# MainBlock.net
KiCad netlist of a schematic drawn in Altium Designer
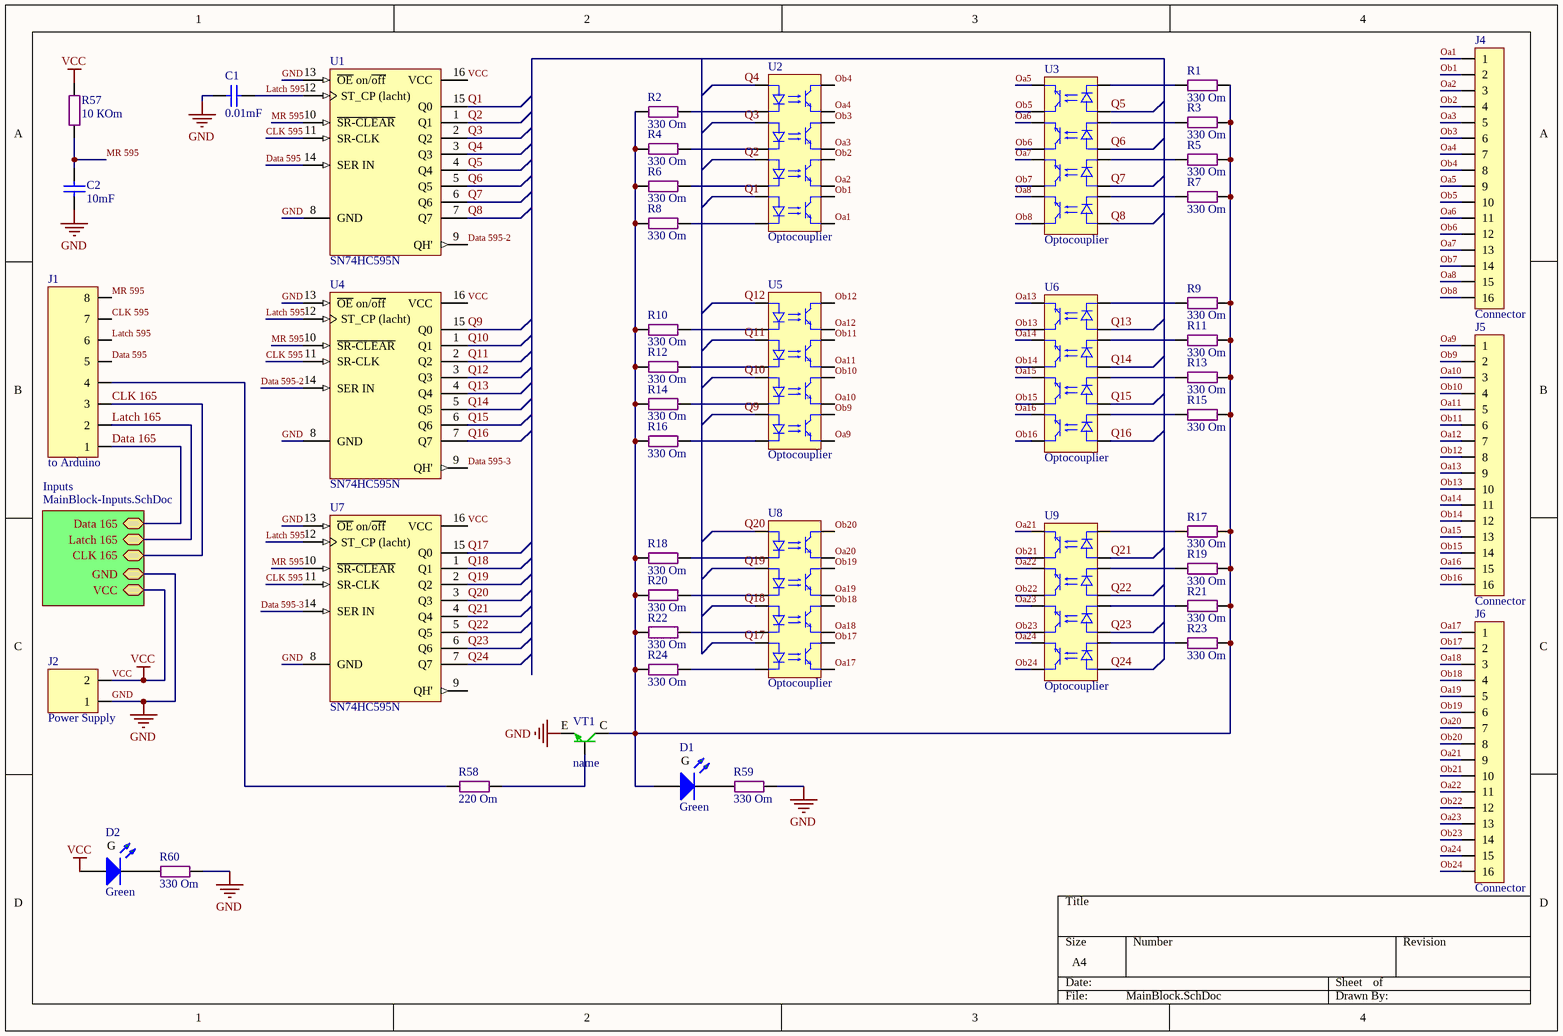
[diagram p0: MainBlock.SchDoc]

(export (version "E")
  (design (tool "Eeschema 10.0.6"))
  (components
    (comp (ref "C1")
      (value "0.01mF")
      (footprint "bj Lib:Cap (3p)")
      (description "Capacitor")
      (libsource (lib "bj Lib") (part "Cap"))
    )
    (comp (ref "C2")
      (value "10mF")
      (footprint "bj Lib:Cap p2.54mm (2p)")
      (description "Capacitor")
      (libsource (lib "ss_ServersControl") (part "Cap"))
    )
    (comp (ref "D1")
      (value "Green")
      (footprint "LED:LED SMD 0805 Green")
      (description "?2v ?20mA")
      (libsource (lib "LED") (part "Led SMD 0805 Green"))
    )
    (comp (ref "D2")
      (value "Green")
      (footprint "LED:LED SMD 0805 Green")
      (description "?2v ?20mA")
      (libsource (lib "LED") (part "Led SMD 0805 Green"))
    )
    (comp (ref "J1")
      (value "to Arduino")
      (footprint "bj Lib:Line 2.54 x 8")
      (description "8pin Connector")
      (libsource (lib "bj Lib") (part "Connector ( 8 pin )"))
    )
    (comp (ref "J2")
      (value "Power Supply")
      (footprint "bj Lib:Line 2.54 x 2")
      (description "8pin Connector")
      (libsource (lib "bj Lib") (part "Connector ( 2 pin )"))
    )
    (comp (ref "J4")
      (value "Connector")
      (footprint "bj Lib:LINE 2.54 x 8D mirrored")
      (description "16pin Connector")
      (libsource (lib "ss_ServersControl") (part "Connector Dbl ( 16 pin )"))
    )
    (comp (ref "J5")
      (value "Connector")
      (footprint "bj Lib:LINE 2.54 x 8D mirrored")
      (description "16pin Connector")
      (libsource (lib "ss_ServersControl") (part "Connector Dbl ( 16 pin )"))
    )
    (comp (ref "J6")
      (value "Connector")
      (footprint "bj Lib:LINE 2.54 x 8D mirrored")
      (description "16pin Connector")
      (libsource (lib "ss_ServersControl") (part "Connector Dbl ( 16 pin )"))
    )
    (comp (ref "R1")
      (value "330 Om")
      (footprint "Res p7.62 (4p)")
      (libsource (lib "bj Lib") (part "Resistor"))
    )
    (comp (ref "R2")
      (value "330 Om")
      (footprint "Res p7.62 (4p)")
      (libsource (lib "bj Lib") (part "Resistor"))
    )
    (comp (ref "R3")
      (value "330 Om")
      (footprint "Res p7.62 (4p)")
      (libsource (lib "bj Lib") (part "Resistor"))
    )
    (comp (ref "R4")
      (value "330 Om")
      (footprint "Res p7.62 (4p)")
      (libsource (lib "bj Lib") (part "Resistor"))
    )
    (comp (ref "R5")
      (value "330 Om")
      (footprint "Res p7.62 (4p)")
      (libsource (lib "bj Lib") (part "Resistor"))
    )
    (comp (ref "R6")
      (value "330 Om")
      (footprint "Res p7.62 (4p)")
      (libsource (lib "bj Lib") (part "Resistor"))
    )
    (comp (ref "R7")
      (value "330 Om")
      (footprint "Res p7.62 (4p)")
      (libsource (lib "bj Lib") (part "Resistor"))
    )
    (comp (ref "R8")
      (value "330 Om")
      (footprint "Res p7.62 (4p)")
      (libsource (lib "bj Lib") (part "Resistor"))
    )
    (comp (ref "R9")
      (value "330 Om")
      (footprint "Res p7.62 (4p)")
      (libsource (lib "bj Lib") (part "Resistor"))
    )
    (comp (ref "R10")
      (value "330 Om")
      (footprint "Res p7.62 (4p)")
      (libsource (lib "bj Lib") (part "Resistor"))
    )
    (comp (ref "R11")
      (value "330 Om")
      (footprint "Res p7.62 (4p)")
      (libsource (lib "bj Lib") (part "Resistor"))
    )
    (comp (ref "R12")
      (value "330 Om")
      (footprint "Res p7.62 (4p)")
      (libsource (lib "bj Lib") (part "Resistor"))
    )
    (comp (ref "R13")
      (value "330 Om")
      (footprint "Res p7.62 (4p)")
      (libsource (lib "bj Lib") (part "Resistor"))
    )
    (comp (ref "R14")
      (value "330 Om")
      (footprint "Res p7.62 (4p)")
      (libsource (lib "bj Lib") (part "Resistor"))
    )
    (comp (ref "R15")
      (value "330 Om")
      (footprint "Res p7.62 (4p)")
      (libsource (lib "bj Lib") (part "Resistor"))
    )
    (comp (ref "R16")
      (value "330 Om")
      (footprint "Res p7.62 (4p)")
      (libsource (lib "bj Lib") (part "Resistor"))
    )
    (comp (ref "R17")
      (value "330 Om")
      (footprint "Res p7.62 (4p)")
      (libsource (lib "bj Lib") (part "Resistor"))
    )
    (comp (ref "R18")
      (value "330 Om")
      (footprint "Res p7.62 (4p)")
      (libsource (lib "bj Lib") (part "Resistor"))
    )
    (comp (ref "R19")
      (value "330 Om")
      (footprint "Res p7.62 (4p)")
      (libsource (lib "bj Lib") (part "Resistor"))
    )
    (comp (ref "R20")
      (value "330 Om")
      (footprint "Res p7.62 (4p)")
      (libsource (lib "bj Lib") (part "Resistor"))
    )
    (comp (ref "R21")
      (value "330 Om")
      (footprint "Res p7.62 (4p)")
      (libsource (lib "bj Lib") (part "Resistor"))
    )
    (comp (ref "R22")
      (value "330 Om")
      (footprint "Res p7.62 (4p)")
      (libsource (lib "bj Lib") (part "Resistor"))
    )
    (comp (ref "R23")
      (value "330 Om")
      (footprint "Res p7.62 (4p)")
      (libsource (lib "bj Lib") (part "Resistor"))
    )
    (comp (ref "R24")
      (value "330 Om")
      (footprint "Res p7.62 (4p)")
      (libsource (lib "bj Lib") (part "Resistor"))
    )
    (comp (ref "R57")
      (value "10 КOm")
      (footprint "Res p7.62 (4p)")
      (libsource (lib "ss_ServersControl") (part "Resistor"))
    )
    (comp (ref "R58")
      (value "220 Om")
      (footprint "Res p7.62 (4p)")
      (libsource (lib "ss_ServersControl") (part "Resistor"))
    )
    (comp (ref "R59")
      (value "330 Om")
      (footprint "bj Lib:SMD 0603 (1608)")
      (libsource (lib "ss_ServersControl") (part "Resistor"))
    )
    (comp (ref "R60")
      (value "330 Om")
      (footprint "bj Lib:SMD 0603 (1608)")
      (libsource (lib "ss_ServersControl") (part "Resistor"))
    )
    (comp (ref "U1")
      (value "SN74HC595N")
      (footprint "bj Lib:DIP16")
      (description "8-Bit Shift Register with 3-State Output Registers")
      (fields (field (name "PUBLISHER") "Altium Limited"))
      (libsource (lib "bj Lib") (part "SN74HC595N"))
    )
    (comp (ref "U2")
      (value "Optocouplier")
      (footprint "bj Lib:DIP16")
      (description "4x channel")
      (libsource (lib "bj Lib") (part "Optocouplier 4x"))
    )
    (comp (ref "U3")
      (value "Optocouplier")
      (footprint "bj Lib:DIP16")
      (description "4x channel")
      (libsource (lib "bj Lib") (part "Optocouplier 4x"))
    )
    (comp (ref "U4")
      (value "SN74HC595N")
      (footprint "bj Lib:DIP16")
      (description "8-Bit Shift Register with 3-State Output Registers")
      (fields (field (name "PUBLISHER") "Altium Limited"))
      (libsource (lib "bj Lib") (part "SN74HC595N"))
    )
    (comp (ref "U5")
      (value "Optocouplier")
      (footprint "bj Lib:DIP16")
      (description "4x channel")
      (libsource (lib "bj Lib") (part "Optocouplier 4x"))
    )
    (comp (ref "U6")
      (value "Optocouplier")
      (footprint "bj Lib:DIP16")
      (description "4x channel")
      (libsource (lib "bj Lib") (part "Optocouplier 4x"))
    )
    (comp (ref "U7")
      (value "SN74HC595N")
      (footprint "bj Lib:DIP16")
      (description "8-Bit Shift Register with 3-State Output Registers")
      (fields (field (name "PUBLISHER") "Altium Limited"))
      (libsource (lib "bj Lib") (part "SN74HC595N"))
    )
    (comp (ref "U8")
      (value "Optocouplier")
      (footprint "bj Lib:DIP16")
      (description "4x channel")
      (libsource (lib "bj Lib") (part "Optocouplier 4x"))
    )
    (comp (ref "U9")
      (value "Optocouplier")
      (footprint "bj Lib:DIP16")
      (description "4x channel")
      (libsource (lib "bj Lib") (part "Optocouplier 4x"))
    )
    (comp (ref "VT1") (value "name") (footprint "Trnstr (3p) ECB") (libsource (lib "bj Lib") (part "NPN")))
  )
  (nets
    (net (code "1") (name "/CLK 165") (class "Default")
      (node (ref "J1") (pin "3") (pinfunction "3_3") (pintype "passive"))
    )
    (net (code "2") (name "/CLK 595") (class "Default")
      (node (ref "J1") (pin "7") (pinfunction "7_7") (pintype "passive"))
      (node (ref "U1") (pin "11") (pinfunction "SR-CLK_11") (pintype "input"))
      (node (ref "U4") (pin "11") (pinfunction "SR-CLK_11") (pintype "input"))
      (node (ref "U7") (pin "11") (pinfunction "SR-CLK_11") (pintype "input"))
    )
    (net (code "3") (name "/Data 165") (class "Default")
      (node (ref "J1") (pin "1") (pinfunction "1_1") (pintype "passive"))
    )
    (net (code "4") (name "/Data 595") (class "Default")
      (node (ref "J1") (pin "5") (pinfunction "5_5") (pintype "passive"))
      (node (ref "U1") (pin "14") (pinfunction "SER_IN_14") (pintype "input"))
    )
    (net (code "5") (name "/Data 595-2") (class "Default")
      (node (ref "U1") (pin "9") (pinfunction "QH'_9") (pintype "output"))
      (node (ref "U4") (pin "14") (pinfunction "SER_IN_14") (pintype "input"))
    )
    (net (code "6") (name "/Data 595-3") (class "Default")
      (node (ref "U4") (pin "9") (pinfunction "QH'_9") (pintype "output"))
      (node (ref "U7") (pin "14") (pinfunction "SER_IN_14") (pintype "input"))
    )
    (net (code "7") (name "/Latch 165") (class "Default")
      (node (ref "J1") (pin "2") (pinfunction "2_2") (pintype "passive"))
    )
    (net (code "8") (name "/Latch 595") (class "Default")
      (node (ref "C1") (pin "1") (pinfunction "1_1") (pintype "passive"))
      (node (ref "J1") (pin "6") (pinfunction "6_6") (pintype "passive"))
      (node (ref "U1") (pin "12") (pinfunction "ST_CP_(lacht)_12") (pintype "input"))
      (node (ref "U4") (pin "12") (pinfunction "ST_CP_(lacht)_12") (pintype "input"))
      (node (ref "U7") (pin "12") (pinfunction "ST_CP_(lacht)_12") (pintype "input"))
    )
    (net (code "9") (name "/MR 595") (class "Default")
      (node (ref "C2") (pin "2") (pinfunction "2_2") (pintype "passive"))
      (node (ref "J1") (pin "8") (pinfunction "8_8") (pintype "passive"))
      (node (ref "R57") (pin "2") (pinfunction "2_2") (pintype "passive"))
      (node (ref "U1") (pin "10") (pinfunction "~{SR-CLEAR}_10") (pintype "input"))
      (node (ref "U4") (pin "10") (pinfunction "~{SR-CLEAR}_10") (pintype "input"))
      (node (ref "U7") (pin "10") (pinfunction "~{SR-CLEAR}_10") (pintype "input"))
    )
    (net (code "10") (name "/Oa1") (class "Default")
      (node (ref "J4") (pin "1") (pinfunction "1_1") (pintype "passive"))
      (node (ref "U2") (pin "9") (pinfunction "9_9") (pintype "passive"))
    )
    (net (code "11") (name "/Oa2") (class "Default")
      (node (ref "J4") (pin "3") (pinfunction "3_3") (pintype "passive"))
      (node (ref "U2") (pin "11") (pinfunction "11_11") (pintype "passive"))
    )
    (net (code "12") (name "/Oa3") (class "Default")
      (node (ref "J4") (pin "5") (pinfunction "5_5") (pintype "passive"))
      (node (ref "U2") (pin "13") (pinfunction "13_13") (pintype "passive"))
    )
    (net (code "13") (name "/Oa4") (class "Default")
      (node (ref "J4") (pin "7") (pinfunction "7_7") (pintype "passive"))
      (node (ref "U2") (pin "15") (pinfunction "15_15") (pintype "passive"))
    )
    (net (code "14") (name "/Oa5") (class "Default")
      (node (ref "J4") (pin "9") (pinfunction "9_9") (pintype "passive"))
      (node (ref "U3") (pin "9") (pinfunction "9_9") (pintype "passive"))
    )
    (net (code "15") (name "/Oa6") (class "Default")
      (node (ref "J4") (pin "11") (pinfunction "11_11") (pintype "passive"))
      (node (ref "U3") (pin "11") (pinfunction "11_11") (pintype "passive"))
    )
    (net (code "16") (name "/Oa7") (class "Default")
      (node (ref "J4") (pin "13") (pinfunction "13_13") (pintype "passive"))
      (node (ref "U3") (pin "13") (pinfunction "13_13") (pintype "passive"))
    )
    (net (code "17") (name "/Oa8") (class "Default")
      (node (ref "J4") (pin "15") (pinfunction "15_15") (pintype "passive"))
      (node (ref "U3") (pin "15") (pinfunction "15_15") (pintype "passive"))
    )
    (net (code "18") (name "/Oa9") (class "Default")
      (node (ref "J5") (pin "1") (pinfunction "1_1") (pintype "passive"))
      (node (ref "U5") (pin "9") (pinfunction "9_9") (pintype "passive"))
    )
    (net (code "19") (name "/Oa10") (class "Default")
      (node (ref "J5") (pin "3") (pinfunction "3_3") (pintype "passive"))
      (node (ref "U5") (pin "11") (pinfunction "11_11") (pintype "passive"))
    )
    (net (code "20") (name "/Oa11") (class "Default")
      (node (ref "J5") (pin "5") (pinfunction "5_5") (pintype "passive"))
      (node (ref "U5") (pin "13") (pinfunction "13_13") (pintype "passive"))
    )
    (net (code "21") (name "/Oa12") (class "Default")
      (node (ref "J5") (pin "7") (pinfunction "7_7") (pintype "passive"))
      (node (ref "U5") (pin "15") (pinfunction "15_15") (pintype "passive"))
    )
    (net (code "22") (name "/Oa13") (class "Default")
      (node (ref "J5") (pin "9") (pinfunction "9_9") (pintype "passive"))
      (node (ref "U6") (pin "9") (pinfunction "9_9") (pintype "passive"))
    )
    (net (code "23") (name "/Oa14") (class "Default")
      (node (ref "J5") (pin "11") (pinfunction "11_11") (pintype "passive"))
      (node (ref "U6") (pin "11") (pinfunction "11_11") (pintype "passive"))
    )
    (net (code "24") (name "/Oa15") (class "Default")
      (node (ref "J5") (pin "13") (pinfunction "13_13") (pintype "passive"))
      (node (ref "U6") (pin "13") (pinfunction "13_13") (pintype "passive"))
    )
    (net (code "25") (name "/Oa16") (class "Default")
      (node (ref "J5") (pin "15") (pinfunction "15_15") (pintype "passive"))
      (node (ref "U6") (pin "15") (pinfunction "15_15") (pintype "passive"))
    )
    (net (code "26") (name "/Oa17") (class "Default")
      (node (ref "J6") (pin "1") (pinfunction "1_1") (pintype "passive"))
      (node (ref "U8") (pin "9") (pinfunction "9_9") (pintype "passive"))
    )
    (net (code "27") (name "/Oa18") (class "Default")
      (node (ref "J6") (pin "3") (pinfunction "3_3") (pintype "passive"))
      (node (ref "U8") (pin "11") (pinfunction "11_11") (pintype "passive"))
    )
    (net (code "28") (name "/Oa19") (class "Default")
      (node (ref "J6") (pin "5") (pinfunction "5_5") (pintype "passive"))
      (node (ref "U8") (pin "13") (pinfunction "13_13") (pintype "passive"))
    )
    (net (code "29") (name "/Oa20") (class "Default")
      (node (ref "J6") (pin "7") (pinfunction "7_7") (pintype "passive"))
      (node (ref "U8") (pin "15") (pinfunction "15_15") (pintype "passive"))
    )
    (net (code "30") (name "/Oa21") (class "Default")
      (node (ref "J6") (pin "9") (pinfunction "9_9") (pintype "passive"))
      (node (ref "U9") (pin "9") (pinfunction "9_9") (pintype "passive"))
    )
    (net (code "31") (name "/Oa22") (class "Default")
      (node (ref "J6") (pin "11") (pinfunction "11_11") (pintype "passive"))
      (node (ref "U9") (pin "11") (pinfunction "11_11") (pintype "passive"))
    )
    (net (code "32") (name "/Oa23") (class "Default")
      (node (ref "J6") (pin "13") (pinfunction "13_13") (pintype "passive"))
      (node (ref "U9") (pin "13") (pinfunction "13_13") (pintype "passive"))
    )
    (net (code "33") (name "/Oa24") (class "Default")
      (node (ref "J6") (pin "15") (pinfunction "15_15") (pintype "passive"))
      (node (ref "U9") (pin "15") (pinfunction "15_15") (pintype "passive"))
    )
    (net (code "34") (name "/Ob1") (class "Default")
      (node (ref "J4") (pin "2") (pinfunction "2_2") (pintype "passive"))
      (node (ref "U2") (pin "10") (pinfunction "10_10") (pintype "passive"))
    )
    (net (code "35") (name "/Ob2") (class "Default")
      (node (ref "J4") (pin "4") (pinfunction "4_4") (pintype "passive"))
      (node (ref "U2") (pin "12") (pinfunction "12_12") (pintype "passive"))
    )
    (net (code "36") (name "/Ob3") (class "Default")
      (node (ref "J4") (pin "6") (pinfunction "6_6") (pintype "passive"))
      (node (ref "U2") (pin "14") (pinfunction "14_14") (pintype "passive"))
    )
    (net (code "37") (name "/Ob4") (class "Default")
      (node (ref "J4") (pin "8") (pinfunction "8_8") (pintype "passive"))
      (node (ref "U2") (pin "16") (pinfunction "16_16") (pintype "passive"))
    )
    (net (code "38") (name "/Ob5") (class "Default")
      (node (ref "J4") (pin "10") (pinfunction "10_10") (pintype "passive"))
      (node (ref "U3") (pin "10") (pinfunction "10_10") (pintype "passive"))
    )
    (net (code "39") (name "/Ob6") (class "Default")
      (node (ref "J4") (pin "12") (pinfunction "12_12") (pintype "passive"))
      (node (ref "U3") (pin "12") (pinfunction "12_12") (pintype "passive"))
    )
    (net (code "40") (name "/Ob7") (class "Default")
      (node (ref "J4") (pin "14") (pinfunction "14_14") (pintype "passive"))
      (node (ref "U3") (pin "14") (pinfunction "14_14") (pintype "passive"))
    )
    (net (code "41") (name "/Ob8") (class "Default")
      (node (ref "J4") (pin "16") (pinfunction "16_16") (pintype "passive"))
      (node (ref "U3") (pin "16") (pinfunction "16_16") (pintype "passive"))
    )
    (net (code "42") (name "/Ob9") (class "Default")
      (node (ref "J5") (pin "2") (pinfunction "2_2") (pintype "passive"))
      (node (ref "U5") (pin "10") (pinfunction "10_10") (pintype "passive"))
    )
    (net (code "43") (name "/Ob10") (class "Default")
      (node (ref "J5") (pin "4") (pinfunction "4_4") (pintype "passive"))
      (node (ref "U5") (pin "12") (pinfunction "12_12") (pintype "passive"))
    )
    (net (code "44") (name "/Ob11") (class "Default")
      (node (ref "J5") (pin "6") (pinfunction "6_6") (pintype "passive"))
      (node (ref "U5") (pin "14") (pinfunction "14_14") (pintype "passive"))
    )
    (net (code "45") (name "/Ob12") (class "Default")
      (node (ref "J5") (pin "8") (pinfunction "8_8") (pintype "passive"))
      (node (ref "U5") (pin "16") (pinfunction "16_16") (pintype "passive"))
    )
    (net (code "46") (name "/Ob13") (class "Default")
      (node (ref "J5") (pin "10") (pinfunction "10_10") (pintype "passive"))
      (node (ref "U6") (pin "10") (pinfunction "10_10") (pintype "passive"))
    )
    (net (code "47") (name "/Ob14") (class "Default")
      (node (ref "J5") (pin "12") (pinfunction "12_12") (pintype "passive"))
      (node (ref "U6") (pin "12") (pinfunction "12_12") (pintype "passive"))
    )
    (net (code "48") (name "/Ob15") (class "Default")
      (node (ref "J5") (pin "14") (pinfunction "14_14") (pintype "passive"))
      (node (ref "U6") (pin "14") (pinfunction "14_14") (pintype "passive"))
    )
    (net (code "49") (name "/Ob16") (class "Default")
      (node (ref "J5") (pin "16") (pinfunction "16_16") (pintype "passive"))
      (node (ref "U6") (pin "16") (pinfunction "16_16") (pintype "passive"))
    )
    (net (code "50") (name "/Ob17") (class "Default")
      (node (ref "J6") (pin "2") (pinfunction "2_2") (pintype "passive"))
      (node (ref "U8") (pin "10") (pinfunction "10_10") (pintype "passive"))
    )
    (net (code "51") (name "/Ob18") (class "Default")
      (node (ref "J6") (pin "4") (pinfunction "4_4") (pintype "passive"))
      (node (ref "U8") (pin "12") (pinfunction "12_12") (pintype "passive"))
    )
    (net (code "52") (name "/Ob19") (class "Default")
      (node (ref "J6") (pin "6") (pinfunction "6_6") (pintype "passive"))
      (node (ref "U8") (pin "14") (pinfunction "14_14") (pintype "passive"))
    )
    (net (code "53") (name "/Ob20") (class "Default")
      (node (ref "J6") (pin "8") (pinfunction "8_8") (pintype "passive"))
      (node (ref "U8") (pin "16") (pinfunction "16_16") (pintype "passive"))
    )
    (net (code "54") (name "/Ob21") (class "Default")
      (node (ref "J6") (pin "10") (pinfunction "10_10") (pintype "passive"))
      (node (ref "U9") (pin "10") (pinfunction "10_10") (pintype "passive"))
    )
    (net (code "55") (name "/Ob22") (class "Default")
      (node (ref "J6") (pin "12") (pinfunction "12_12") (pintype "passive"))
      (node (ref "U9") (pin "12") (pinfunction "12_12") (pintype "passive"))
    )
    (net (code "56") (name "/Ob23") (class "Default")
      (node (ref "J6") (pin "14") (pinfunction "14_14") (pintype "passive"))
      (node (ref "U9") (pin "14") (pinfunction "14_14") (pintype "passive"))
    )
    (net (code "57") (name "/Ob24") (class "Default")
      (node (ref "J6") (pin "16") (pinfunction "16_16") (pintype "passive"))
      (node (ref "U9") (pin "16") (pinfunction "16_16") (pintype "passive"))
    )
    (net (code "58") (name "/Q1") (class "Default")
      (node (ref "U1") (pin "15") (pinfunction "Q0_15") (pintype "tri_state"))
      (node (ref "U2") (pin "7") (pinfunction "7_7") (pintype "passive"))
    )
    (net (code "59") (name "/Q2") (class "Default")
      (node (ref "U1") (pin "1") (pinfunction "Q1_1") (pintype "tri_state"))
      (node (ref "U2") (pin "5") (pinfunction "5_5") (pintype "passive"))
    )
    (net (code "60") (name "/Q3") (class "Default")
      (node (ref "U1") (pin "2") (pinfunction "Q2_2") (pintype "tri_state"))
      (node (ref "U2") (pin "3") (pinfunction "3_3") (pintype "passive"))
    )
    (net (code "61") (name "/Q4") (class "Default")
      (node (ref "U1") (pin "3") (pinfunction "Q3_3") (pintype "tri_state"))
      (node (ref "U2") (pin "1") (pinfunction "1_1") (pintype "passive"))
    )
    (net (code "62") (name "/Q5") (class "Default")
      (node (ref "U1") (pin "4") (pinfunction "Q4_4") (pintype "tri_state"))
      (node (ref "U3") (pin "7") (pinfunction "7_7") (pintype "passive"))
    )
    (net (code "63") (name "/Q6") (class "Default")
      (node (ref "U1") (pin "5") (pinfunction "Q5_5") (pintype "tri_state"))
      (node (ref "U3") (pin "5") (pinfunction "5_5") (pintype "passive"))
    )
    (net (code "64") (name "/Q7") (class "Default")
      (node (ref "U1") (pin "6") (pinfunction "Q6_6") (pintype "tri_state"))
      (node (ref "U3") (pin "3") (pinfunction "3_3") (pintype "passive"))
    )
    (net (code "65") (name "/Q8") (class "Default")
      (node (ref "U1") (pin "7") (pinfunction "Q7_7") (pintype "tri_state"))
      (node (ref "U3") (pin "1") (pinfunction "1_1") (pintype "passive"))
    )
    (net (code "66") (name "/Q9") (class "Default")
      (node (ref "U4") (pin "15") (pinfunction "Q0_15") (pintype "tri_state"))
      (node (ref "U5") (pin "7") (pinfunction "7_7") (pintype "passive"))
    )
    (net (code "67") (name "/Q10") (class "Default")
      (node (ref "U4") (pin "1") (pinfunction "Q1_1") (pintype "tri_state"))
      (node (ref "U5") (pin "5") (pinfunction "5_5") (pintype "passive"))
    )
    (net (code "68") (name "/Q11") (class "Default")
      (node (ref "U4") (pin "2") (pinfunction "Q2_2") (pintype "tri_state"))
      (node (ref "U5") (pin "3") (pinfunction "3_3") (pintype "passive"))
    )
    (net (code "69") (name "/Q12") (class "Default")
      (node (ref "U4") (pin "3") (pinfunction "Q3_3") (pintype "tri_state"))
      (node (ref "U5") (pin "1") (pinfunction "1_1") (pintype "passive"))
    )
    (net (code "70") (name "/Q13") (class "Default")
      (node (ref "U4") (pin "4") (pinfunction "Q4_4") (pintype "tri_state"))
      (node (ref "U6") (pin "7") (pinfunction "7_7") (pintype "passive"))
    )
    (net (code "71") (name "/Q14") (class "Default")
      (node (ref "U4") (pin "5") (pinfunction "Q5_5") (pintype "tri_state"))
      (node (ref "U6") (pin "5") (pinfunction "5_5") (pintype "passive"))
    )
    (net (code "72") (name "/Q15") (class "Default")
      (node (ref "U4") (pin "6") (pinfunction "Q6_6") (pintype "tri_state"))
      (node (ref "U6") (pin "3") (pinfunction "3_3") (pintype "passive"))
    )
    (net (code "73") (name "/Q16") (class "Default")
      (node (ref "U4") (pin "7") (pinfunction "Q7_7") (pintype "tri_state"))
      (node (ref "U6") (pin "1") (pinfunction "1_1") (pintype "passive"))
    )
    (net (code "74") (name "/Q17") (class "Default")
      (node (ref "U7") (pin "15") (pinfunction "Q0_15") (pintype "tri_state"))
      (node (ref "U8") (pin "7") (pinfunction "7_7") (pintype "passive"))
    )
    (net (code "75") (name "/Q18") (class "Default")
      (node (ref "U7") (pin "1") (pinfunction "Q1_1") (pintype "tri_state"))
      (node (ref "U8") (pin "5") (pinfunction "5_5") (pintype "passive"))
    )
    (net (code "76") (name "/Q19") (class "Default")
      (node (ref "U7") (pin "2") (pinfunction "Q2_2") (pintype "tri_state"))
      (node (ref "U8") (pin "3") (pinfunction "3_3") (pintype "passive"))
    )
    (net (code "77") (name "/Q20") (class "Default")
      (node (ref "U7") (pin "3") (pinfunction "Q3_3") (pintype "tri_state"))
      (node (ref "U8") (pin "1") (pinfunction "1_1") (pintype "passive"))
    )
    (net (code "78") (name "/Q21") (class "Default")
      (node (ref "U7") (pin "4") (pinfunction "Q4_4") (pintype "tri_state"))
      (node (ref "U9") (pin "7") (pinfunction "7_7") (pintype "passive"))
    )
    (net (code "79") (name "/Q22") (class "Default")
      (node (ref "U7") (pin "5") (pinfunction "Q5_5") (pintype "tri_state"))
      (node (ref "U9") (pin "5") (pinfunction "5_5") (pintype "passive"))
    )
    (net (code "80") (name "/Q23") (class "Default")
      (node (ref "U7") (pin "6") (pinfunction "Q6_6") (pintype "tri_state"))
      (node (ref "U9") (pin "3") (pinfunction "3_3") (pintype "passive"))
    )
    (net (code "81") (name "/Q24") (class "Default")
      (node (ref "U7") (pin "7") (pinfunction "Q7_7") (pintype "tri_state"))
      (node (ref "U9") (pin "1") (pinfunction "1_1") (pintype "passive"))
    )
    (net (code "82") (name "GND") (class "Default")
      (node (ref "C1") (pin "2") (pinfunction "2_2") (pintype "passive"))
      (node (ref "C2") (pin "1") (pinfunction "1_1") (pintype "passive"))
      (node (ref "J2") (pin "1") (pinfunction "1_1") (pintype "passive"))
      (node (ref "R59") (pin "2") (pinfunction "2_2") (pintype "passive"))
      (node (ref "R60") (pin "2") (pinfunction "2_2") (pintype "passive"))
      (node (ref "U1") (pin "13") (pinfunction "~{OE}_on/~{off}_13") (pintype "input"))
      (node (ref "U1") (pin "8") (pinfunction "GND_8") (pintype "power_in"))
      (node (ref "U4") (pin "13") (pinfunction "~{OE}_on/~{off}_13") (pintype "input"))
      (node (ref "U4") (pin "8") (pinfunction "GND_8") (pintype "power_in"))
      (node (ref "U7") (pin "13") (pinfunction "~{OE}_on/~{off}_13") (pintype "input"))
      (node (ref "U7") (pin "8") (pinfunction "GND_8") (pintype "power_in"))
      (node (ref "VT1") (pin "E") (pinfunction "E_E") (pintype "passive"))
    )
    (net (code "83") (name "Net-(D1-PadA)") (class "Default")
      (node (ref "D1") (pin "A") (pinfunction "A_A") (pintype "passive"))
      (node (ref "R1") (pin "1") (pinfunction "1_1") (pintype "passive"))
      (node (ref "R10") (pin "1") (pinfunction "1_1") (pintype "passive"))
      (node (ref "R11") (pin "1") (pinfunction "1_1") (pintype "passive"))
      (node (ref "R12") (pin "1") (pinfunction "1_1") (pintype "passive"))
      (node (ref "R13") (pin "1") (pinfunction "1_1") (pintype "passive"))
      (node (ref "R14") (pin "1") (pinfunction "1_1") (pintype "passive"))
      (node (ref "R15") (pin "1") (pinfunction "1_1") (pintype "passive"))
      (node (ref "R16") (pin "1") (pinfunction "1_1") (pintype "passive"))
      (node (ref "R17") (pin "1") (pinfunction "1_1") (pintype "passive"))
      (node (ref "R18") (pin "1") (pinfunction "1_1") (pintype "passive"))
      (node (ref "R19") (pin "1") (pinfunction "1_1") (pintype "passive"))
      (node (ref "R2") (pin "1") (pinfunction "1_1") (pintype "passive"))
      (node (ref "R20") (pin "1") (pinfunction "1_1") (pintype "passive"))
      (node (ref "R21") (pin "1") (pinfunction "1_1") (pintype "passive"))
      (node (ref "R22") (pin "1") (pinfunction "1_1") (pintype "passive"))
      (node (ref "R23") (pin "1") (pinfunction "1_1") (pintype "passive"))
      (node (ref "R24") (pin "1") (pinfunction "1_1") (pintype "passive"))
      (node (ref "R3") (pin "1") (pinfunction "1_1") (pintype "passive"))
      (node (ref "R4") (pin "1") (pinfunction "1_1") (pintype "passive"))
      (node (ref "R5") (pin "1") (pinfunction "1_1") (pintype "passive"))
      (node (ref "R6") (pin "1") (pinfunction "1_1") (pintype "passive"))
      (node (ref "R7") (pin "1") (pinfunction "1_1") (pintype "passive"))
      (node (ref "R8") (pin "1") (pinfunction "1_1") (pintype "passive"))
      (node (ref "R9") (pin "1") (pinfunction "1_1") (pintype "passive"))
      (node (ref "VT1") (pin "C") (pinfunction "C_C") (pintype "passive"))
    )
    (net (code "84") (name "Net-(D1-PadK)") (class "Default")
      (node (ref "D1") (pin "K") (pinfunction "K_K") (pintype "passive"))
      (node (ref "R59") (pin "1") (pinfunction "1_1") (pintype "passive"))
    )
    (net (code "85") (name "Net-(D2-PadK)") (class "Default")
      (node (ref "D2") (pin "K") (pinfunction "K_K") (pintype "passive"))
      (node (ref "R60") (pin "1") (pinfunction "1_1") (pintype "passive"))
    )
    (net (code "86") (name "Net-(J1-Pad4)") (class "Default")
      (node (ref "J1") (pin "4") (pinfunction "4_4") (pintype "passive"))
      (node (ref "R58") (pin "1") (pinfunction "1_1") (pintype "passive"))
    )
    (net (code "87") (name "Net-(R1-Pad2)") (class "Default")
      (node (ref "R1") (pin "2") (pinfunction "2_2") (pintype "passive"))
      (node (ref "U3") (pin "8") (pinfunction "8_8") (pintype "passive"))
    )
    (net (code "88") (name "Net-(R2-Pad2)") (class "Default")
      (node (ref "R2") (pin "2") (pinfunction "2_2") (pintype "passive"))
      (node (ref "U2") (pin "2") (pinfunction "2_2") (pintype "passive"))
    )
    (net (code "89") (name "Net-(R3-Pad2)") (class "Default")
      (node (ref "R3") (pin "2") (pinfunction "2_2") (pintype "passive"))
      (node (ref "U3") (pin "6") (pinfunction "6_6") (pintype "passive"))
    )
    (net (code "90") (name "Net-(R4-Pad2)") (class "Default")
      (node (ref "R4") (pin "2") (pinfunction "2_2") (pintype "passive"))
      (node (ref "U2") (pin "4") (pinfunction "4_4") (pintype "passive"))
    )
    (net (code "91") (name "Net-(R5-Pad2)") (class "Default")
      (node (ref "R5") (pin "2") (pinfunction "2_2") (pintype "passive"))
      (node (ref "U3") (pin "4") (pinfunction "4_4") (pintype "passive"))
    )
    (net (code "92") (name "Net-(R6-Pad2)") (class "Default")
      (node (ref "R6") (pin "2") (pinfunction "2_2") (pintype "passive"))
      (node (ref "U2") (pin "6") (pinfunction "6_6") (pintype "passive"))
    )
    (net (code "93") (name "Net-(R7-Pad2)") (class "Default")
      (node (ref "R7") (pin "2") (pinfunction "2_2") (pintype "passive"))
      (node (ref "U3") (pin "2") (pinfunction "2_2") (pintype "passive"))
    )
    (net (code "94") (name "Net-(R8-Pad2)") (class "Default")
      (node (ref "R8") (pin "2") (pinfunction "2_2") (pintype "passive"))
      (node (ref "U2") (pin "8") (pinfunction "8_8") (pintype "passive"))
    )
    (net (code "95") (name "Net-(R9-Pad2)") (class "Default")
      (node (ref "R9") (pin "2") (pinfunction "2_2") (pintype "passive"))
      (node (ref "U6") (pin "8") (pinfunction "8_8") (pintype "passive"))
    )
    (net (code "96") (name "Net-(R10-Pad2)") (class "Default")
      (node (ref "R10") (pin "2") (pinfunction "2_2") (pintype "passive"))
      (node (ref "U5") (pin "2") (pinfunction "2_2") (pintype "passive"))
    )
    (net (code "97") (name "Net-(R11-Pad2)") (class "Default")
      (node (ref "R11") (pin "2") (pinfunction "2_2") (pintype "passive"))
      (node (ref "U6") (pin "6") (pinfunction "6_6") (pintype "passive"))
    )
    (net (code "98") (name "Net-(R12-Pad2)") (class "Default")
      (node (ref "R12") (pin "2") (pinfunction "2_2") (pintype "passive"))
      (node (ref "U5") (pin "4") (pinfunction "4_4") (pintype "passive"))
    )
    (net (code "99") (name "Net-(R13-Pad2)") (class "Default")
      (node (ref "R13") (pin "2") (pinfunction "2_2") (pintype "passive"))
      (node (ref "U6") (pin "4") (pinfunction "4_4") (pintype "passive"))
    )
    (net (code "100") (name "Net-(R14-Pad2)") (class "Default")
      (node (ref "R14") (pin "2") (pinfunction "2_2") (pintype "passive"))
      (node (ref "U5") (pin "6") (pinfunction "6_6") (pintype "passive"))
    )
    (net (code "101") (name "Net-(R15-Pad2)") (class "Default")
      (node (ref "R15") (pin "2") (pinfunction "2_2") (pintype "passive"))
      (node (ref "U6") (pin "2") (pinfunction "2_2") (pintype "passive"))
    )
    (net (code "102") (name "Net-(R16-Pad2)") (class "Default")
      (node (ref "R16") (pin "2") (pinfunction "2_2") (pintype "passive"))
      (node (ref "U5") (pin "8") (pinfunction "8_8") (pintype "passive"))
    )
    (net (code "103") (name "Net-(R17-Pad2)") (class "Default")
      (node (ref "R17") (pin "2") (pinfunction "2_2") (pintype "passive"))
      (node (ref "U9") (pin "8") (pinfunction "8_8") (pintype "passive"))
    )
    (net (code "104") (name "Net-(R18-Pad2)") (class "Default")
      (node (ref "R18") (pin "2") (pinfunction "2_2") (pintype "passive"))
      (node (ref "U8") (pin "2") (pinfunction "2_2") (pintype "passive"))
    )
    (net (code "105") (name "Net-(R19-Pad2)") (class "Default")
      (node (ref "R19") (pin "2") (pinfunction "2_2") (pintype "passive"))
      (node (ref "U9") (pin "6") (pinfunction "6_6") (pintype "passive"))
    )
    (net (code "106") (name "Net-(R20-Pad2)") (class "Default")
      (node (ref "R20") (pin "2") (pinfunction "2_2") (pintype "passive"))
      (node (ref "U8") (pin "4") (pinfunction "4_4") (pintype "passive"))
    )
    (net (code "107") (name "Net-(R21-Pad2)") (class "Default")
      (node (ref "R21") (pin "2") (pinfunction "2_2") (pintype "passive"))
      (node (ref "U9") (pin "4") (pinfunction "4_4") (pintype "passive"))
    )
    (net (code "108") (name "Net-(R22-Pad2)") (class "Default")
      (node (ref "R22") (pin "2") (pinfunction "2_2") (pintype "passive"))
      (node (ref "U8") (pin "6") (pinfunction "6_6") (pintype "passive"))
    )
    (net (code "109") (name "Net-(R23-Pad2)") (class "Default")
      (node (ref "R23") (pin "2") (pinfunction "2_2") (pintype "passive"))
      (node (ref "U9") (pin "2") (pinfunction "2_2") (pintype "passive"))
    )
    (net (code "110") (name "Net-(R24-Pad2)") (class "Default")
      (node (ref "R24") (pin "2") (pinfunction "2_2") (pintype "passive"))
      (node (ref "U8") (pin "8") (pinfunction "8_8") (pintype "passive"))
    )
    (net (code "111") (name "Net-(R58-Pad2)") (class "Default")
      (node (ref "R58") (pin "2") (pinfunction "2_2") (pintype "passive"))
      (node (ref "VT1") (pin "B") (pinfunction "B_B") (pintype "passive"))
    )
    (net (code "112") (name "VCC") (class "Default")
      (node (ref "D2") (pin "A") (pinfunction "A_A") (pintype "passive"))
      (node (ref "J2") (pin "2") (pinfunction "2_2") (pintype "passive"))
      (node (ref "R57") (pin "1") (pinfunction "1_1") (pintype "passive"))
      (node (ref "U1") (pin "16") (pinfunction "VCC_16") (pintype "power_in"))
      (node (ref "U4") (pin "16") (pinfunction "VCC_16") (pintype "power_in"))
      (node (ref "U7") (pin "16") (pinfunction "VCC_16") (pintype "power_in"))
    )
    (net (code "113") (name "unconnected-(U7-QH'-Pad9)") (class "Default")
      (node (ref "U7") (pin "9") (pinfunction "QH'_9") (pintype "output"))
    )
  )
)
